# 08_-_LVDS.net
KiCad netlist of a schematic drawn in Altium Designer
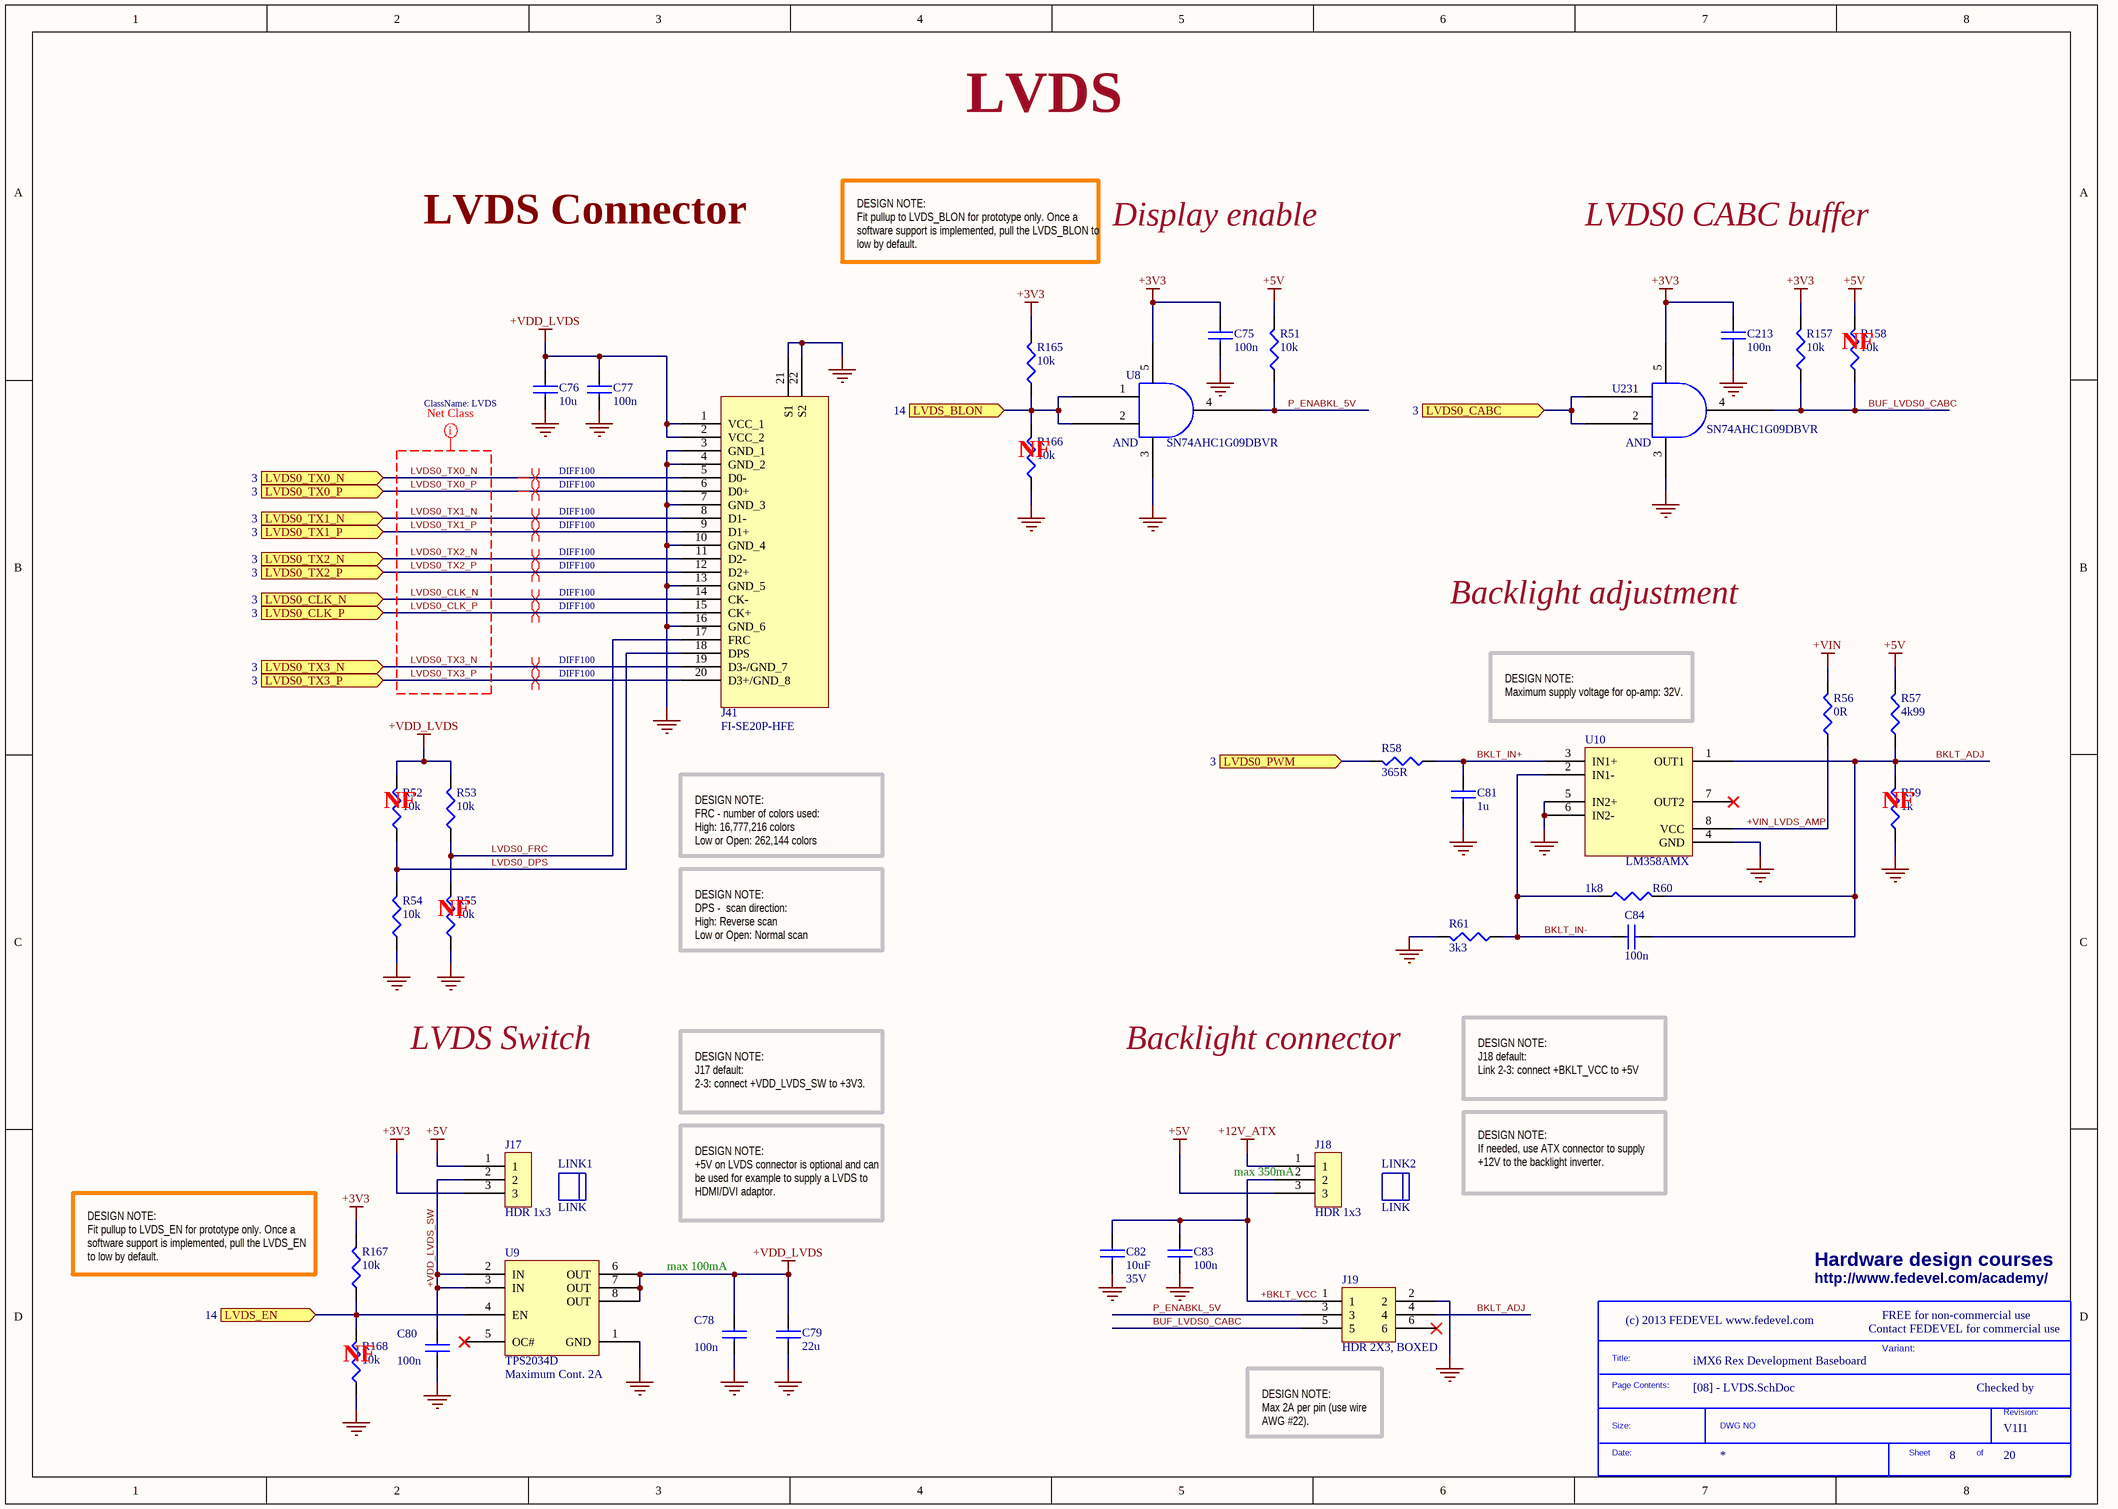
[diagram p0: [08] - LVDS.SchDoc]

(export (version "E")
  (design (tool "Eeschema 10.0.6"))
  (components
    (comp (ref "C75")
      (value "100n")
      (footprint "C0402")
      (description "CAP CER .10UF 50V X5R 10% 0402")
      (fields
        (field (name "MANUFACTURER") "TDK Corporation")
        (field (name "MANUFACTURER PART NUMBER") "C1005X5R1H104K")
      )
      (libsource (lib "Integrated_Library_RF_FEB_2012") (part "C1005X5R1H104K"))
    )
    (comp (ref "C76")
      (value "10u")
      (footprint "C0603")
      (description "CAP CER 10UF 6.3V X5R 20% 0603")
      (fields
        (field (name "MANUFACTURER") "TDK Corporation")
        (field (name "MANUFACTURER PART NUMBER") "C1608X5R0J106M")
      )
      (libsource (lib "Integrated_Library_RF_FEB_2012") (part "C1608X5R0J106M"))
    )
    (comp (ref "C77")
      (value "100n")
      (footprint "C0402")
      (description "CAP CER .10UF 50V X5R 10% 0402")
      (fields
        (field (name "MANUFACTURER") "TDK Corporation")
        (field (name "MANUFACTURER PART NUMBER") "C1005X5R1H104K")
      )
      (libsource (lib "Integrated_Library_RF_FEB_2012") (part "C1005X5R1H104K"))
    )
    (comp (ref "C78")
      (value "100n")
      (footprint "C0402")
      (description "CAP CER .10UF 50V X5R 10% 0402")
      (fields
        (field (name "MANUFACTURER") "TDK Corporation")
        (field (name "MANUFACTURER PART NUMBER") "C1005X5R1H104K")
      )
      (libsource (lib "Integrated_Library_RF_FEB_2012") (part "C1005X5R1H104K"))
    )
    (comp (ref "C79")
      (value "22u")
      (footprint "C0805")
      (description "CAP CER 22UF 16V 10% X5R 0805")
      (fields
        (field (name "MANUFACTURER") "TDK Corporation")
        (field (name "MANUFACTURER PART NUMBER") "C2012X5R1C226K")
        (field (name ".CHECKED PCB") "RF")
        (field (name ".CHECKED SCH") "RF")
      )
      (libsource (lib "Integrated_Library_RF_FEB_2012") (part "C2012X5R1C226K"))
    )
    (comp (ref "C80")
      (value "100n")
      (footprint "C0402")
      (description "CAP CER .10UF 50V X5R 10% 0402")
      (fields
        (field (name "MANUFACTURER") "TDK Corporation")
        (field (name "MANUFACTURER PART NUMBER") "C1005X5R1H104K")
      )
      (libsource (lib "Integrated_Library_RF_FEB_2012") (part "C1005X5R1H104K"))
    )
    (comp (ref "C81")
      (value "1u")
      (footprint "C0402")
      (description "CAP CER 1.0UF 16V X5R 0402")
      (fields
        (field (name "MANUFACTURER") "TDK Corporation")
        (field (name "MANUFACTURER PART NUMBER") "C1005X5R1C105K")
      )
      (libsource (lib "Integrated_Library_RF_FEB_2012") (part "C1005X5R1C105K"))
    )
    (comp (ref "C82")
      (value "10uF")
      (footprint "C1206")
      (description "CAP CER 10UF 35V X5R 1206")
      (fields
        (field (name "MANUFACTURER") "Murata Electronics North America")
        (field (name "MANUFACTURER PART NUMBER") "GRM31CR6YA106KA12L")
        (field (name "VOLTAGE - RATED") "35V")
      )
      (libsource (lib "Integrated_Library_RF_FEB_2012") (part "GRM31CR6YA106KA12L"))
    )
    (comp (ref "C83")
      (value "100n")
      (footprint "C0402")
      (description "CAP CER .10UF 50V X5R 10% 0402")
      (fields
        (field (name "MANUFACTURER") "TDK Corporation")
        (field (name "MANUFACTURER PART NUMBER") "C1005X5R1H104K")
      )
      (libsource (lib "Integrated_Library_RF_FEB_2012") (part "C1005X5R1H104K"))
    )
    (comp (ref "C84")
      (value "100n")
      (footprint "C0402")
      (description "CAP CER .10UF 50V X5R 10% 0402")
      (fields
        (field (name "MANUFACTURER") "TDK Corporation")
        (field (name "MANUFACTURER PART NUMBER") "C1005X5R1H104K")
      )
      (libsource (lib "Integrated_Library_RF_FEB_2012") (part "C1005X5R1H104K"))
    )
    (comp (ref "C213")
      (value "100n")
      (footprint "C0402")
      (description "CAP CER .10UF 50V X5R 10% 0402")
      (fields
        (field (name "MANUFACTURER") "TDK Corporation")
        (field (name "MANUFACTURER PART NUMBER") "C1005X5R1H104K")
      )
      (libsource (lib "Integrated_Library_RF_FEB_2012") (part "C1005X5R1H104K"))
    )
    (comp (ref "J17")
      (value "HDR 1x3")
      (footprint "Hdr_1x3_2.54mm")
      (description "BERGSTIK II .100\" SR STRAIGHT")
      (fields
        (field (name "MANUFACTURER") "FCI")
        (field (name "MANUFACTURER PART NUMBER") "68000-103HLF")
        (field (name ".CREATOR") "MM")
        (field (name ".CHECKED PCB") "MM")
        (field (name ".CHECKED SCH") "MM")
      )
      (libsource (lib "Integrated_Library_RF_FEB_2012") (part "68000-103HLF"))
    )
    (comp (ref "J18")
      (value "HDR 1x3")
      (footprint "Hdr_1x3_2.54mm")
      (description "BERGSTIK II .100\" SR STRAIGHT")
      (fields
        (field (name "MANUFACTURER") "FCI")
        (field (name "MANUFACTURER PART NUMBER") "68000-103HLF")
        (field (name ".CREATOR") "MM")
        (field (name ".CHECKED PCB") "MM")
        (field (name ".CHECKED SCH") "MM")
      )
      (libsource (lib "Integrated_Library_RF_FEB_2012") (part "68000-103HLF"))
    )
    (comp (ref "J19")
      (value "HDR 2X3, BOXED")
      (footprint "HDR_2x3_2.54mm_BOXED")
      (description "CONN HEADER 6POS DL STR GOLD")
      (fields
        (field (name "MANUFACTURER") "3M")
        (field (name "MANUFACTURER PART NUMBER") "30306-6002HB")
        (field (name ".CREATOR") "MM")
        (field (name ".CHECKED PCB") "MM")
        (field (name ".CHECKED SCH") "MM")
      )
      (libsource (lib "Integrated_Library_RF_FEB_2012") (part "30306-6002HB"))
    )
    (comp (ref "J41")
      (value "FI-SE20P-HFE")
      (footprint "FI-SE20P-HFE")
      (description "CONN RCPT 1.25MM 20POS SMD R/A")
      (fields
        (field (name "MANUFACTURER") "JAE Electronics")
        (field (name ".CREATOR") "MM")
        (field (name ".CHECKED PCB") "MM")
        (field (name ".CHECKED SCH") "MM")
      )
      (libsource (lib "Integrated_Library_RF_FEB_2012") (part "FI-SE20P-HFE"))
    )
    (comp (ref "LINK1")
      (value "LINK")
      (description "CONN JUMPER SHORTING .100\" GOLD")
      (fields
        (field (name "MANUFACTURER") "Sullins Connector Solutions")
        (field (name "MANUFACTURER PART NUMBER") "QPC02SXGN-RC")
        (field (name ".CHECKED SCH") "RF")
      )
      (libsource (lib "Integrated_Library_RF_FEB_2012") (part "QPC02SXGN-RC"))
    )
    (comp (ref "LINK2")
      (value "LINK")
      (description "CONN JUMPER SHORTING .100\" GOLD")
      (fields
        (field (name "MANUFACTURER") "Sullins Connector Solutions")
        (field (name "MANUFACTURER PART NUMBER") "QPC02SXGN-RC")
        (field (name ".CHECKED SCH") "RF")
      )
      (libsource (lib "Integrated_Library_RF_FEB_2012") (part "QPC02SXGN-RC"))
    )
    (comp (ref "R51")
      (value "10k")
      (footprint "R0402")
      (description "RES 10.0K OHM 1/16W 1% 0402 SMD")
      (fields
        (field (name "MANUFACTURER") "Yageo")
        (field (name "MANUFACTURER PART NUMBER") "RC0402FR-0710KL")
      )
      (libsource (lib "Integrated_Library_RF_FEB_2012") (part "RC0402FR-0710KL"))
    )
    (comp (ref "R52")
      (value "10k")
      (footprint "R0402")
      (description "RES 10.0K OHM 1/16W 1% 0402 SMD")
      (fields
        (field (name "MANUFACTURER") "Yageo")
        (field (name "MANUFACTURER PART NUMBER") "RC0402FR-0710KL")
      )
      (libsource (lib "Integrated_Library_RF_FEB_2012") (part "RC0402FR-0710KL"))
    )
    (comp (ref "R53")
      (value "10k")
      (footprint "R0402")
      (description "RES 10.0K OHM 1/16W 1% 0402 SMD")
      (fields
        (field (name "MANUFACTURER") "Yageo")
        (field (name "MANUFACTURER PART NUMBER") "RC0402FR-0710KL")
      )
      (libsource (lib "Integrated_Library_RF_FEB_2012") (part "RC0402FR-0710KL"))
    )
    (comp (ref "R54")
      (value "10k")
      (footprint "R0402")
      (description "RES 10.0K OHM 1/16W 1% 0402 SMD")
      (fields
        (field (name "MANUFACTURER") "Yageo")
        (field (name "MANUFACTURER PART NUMBER") "RC0402FR-0710KL")
      )
      (libsource (lib "Integrated_Library_RF_FEB_2012") (part "RC0402FR-0710KL"))
    )
    (comp (ref "R55")
      (value "10k")
      (footprint "R0402")
      (description "RES 10.0K OHM 1/16W 1% 0402 SMD")
      (fields
        (field (name "MANUFACTURER") "Yageo")
        (field (name "MANUFACTURER PART NUMBER") "RC0402FR-0710KL")
      )
      (libsource (lib "Integrated_Library_RF_FEB_2012") (part "RC0402FR-0710KL"))
    )
    (comp (ref "R56")
      (value "0R")
      (footprint "R0402")
      (description "RES 0.0 OHM 1/16W 0402 SMD")
      (fields
        (field (name "MANUFACTURER") "Yageo")
        (field (name "MANUFACTURER PART NUMBER") "RC0402JR-070RL")
      )
      (libsource (lib "Integrated_Library_RF_FEB_2012") (part "RC0402JR-070RL"))
    )
    (comp (ref "R57")
      (value "4k99")
      (footprint "R0402")
      (description "RES TF 4.99K OHM 1% 1/16W 0402")
      (fields
        (field (name "MANUFACTURER") "Stackpole Electronics Inc")
        (field (name "MANUFACTURER PART NUMBER") "RMCF0402FT4K99")
      )
      (libsource (lib "Integrated_Library_RF_FEB_2012") (part "RMCF0402FT4K99"))
    )
    (comp (ref "R58")
      (value "365R")
      (footprint "R0402")
      (description "RES TF 365 OHM 1% 1/16W 0402")
      (fields
        (field (name "MANUFACTURER") "Stackpole Electronics Inc")
        (field (name "MANUFACTURER PART NUMBER") "RMCF0402FT365R")
        (field (name ".CHECKED PCB") "RF")
        (field (name ".CHECKED SCH") "RF")
      )
      (libsource (lib "Integrated_Library_RF_FEB_2012") (part "RMCF0402FT365R"))
    )
    (comp (ref "R59")
      (value "1k")
      (footprint "R0402")
      (description "RES 1.00K OHM 1/16W 1% 0402 SMD")
      (fields
        (field (name "MANUFACTURER") "Yageo")
        (field (name "MANUFACTURER PART NUMBER") "RC0402FR-071KL")
      )
      (libsource (lib "Integrated_Library_RF_FEB_2012") (part "RC0402FR-071KL"))
    )
    (comp (ref "R60")
      (value "1k8")
      (footprint "R0402")
      (description "RES 1.80K OHM 1/16W 1% 0402 SMD")
      (fields
        (field (name "MANUFACTURER") "Vishay Dale")
        (field (name "MANUFACTURER PART NUMBER") "CRCW04021K80FKED")
        (field (name ".CHECKED PCB") "RF")
        (field (name ".CHECKED SCH") "RF")
      )
      (libsource (lib "Integrated_Library_RF_FEB_2012") (part "CRCW04021K80FKED"))
    )
    (comp (ref "R61")
      (value "3k3")
      (footprint "R0402")
      (description "RES 3.30K OHM 1/16W 1% 0402 SMD")
      (fields
        (field (name "MANUFACTURER") "Yageo")
        (field (name "MANUFACTURER PART NUMBER") "RC0402FR-073K3L")
      )
      (libsource (lib "Integrated_Library_RF_FEB_2012") (part "RC0402FR-073K3L"))
    )
    (comp (ref "R157")
      (value "10k")
      (footprint "R0402")
      (description "RES 10.0K OHM 1/16W 1% 0402 SMD")
      (fields
        (field (name "MANUFACTURER") "Yageo")
        (field (name "MANUFACTURER PART NUMBER") "RC0402FR-0710KL")
      )
      (libsource (lib "Integrated_Library_RF_FEB_2012") (part "RC0402FR-0710KL"))
    )
    (comp (ref "R158")
      (value "10k")
      (footprint "R0402")
      (description "RES 10.0K OHM 1/16W 1% 0402 SMD")
      (fields
        (field (name "MANUFACTURER") "Yageo")
        (field (name "MANUFACTURER PART NUMBER") "RC0402FR-0710KL")
      )
      (libsource (lib "Integrated_Library_RF_FEB_2012") (part "RC0402FR-0710KL"))
    )
    (comp (ref "R165")
      (value "10k")
      (footprint "R0402")
      (description "RES 10.0K OHM 1/16W 1% 0402 SMD")
      (fields
        (field (name "MANUFACTURER") "Yageo")
        (field (name "MANUFACTURER PART NUMBER") "RC0402FR-0710KL")
      )
      (libsource (lib "Integrated_Library_RF_FEB_2012") (part "RC0402FR-0710KL"))
    )
    (comp (ref "R166")
      (value "10k")
      (footprint "R0402")
      (description "RES 10.0K OHM 1/16W 1% 0402 SMD")
      (fields
        (field (name "MANUFACTURER") "Yageo")
        (field (name "MANUFACTURER PART NUMBER") "RC0402FR-0710KL")
      )
      (libsource (lib "Integrated_Library_RF_FEB_2012") (part "RC0402FR-0710KL"))
    )
    (comp (ref "R167")
      (value "10k")
      (footprint "R0402")
      (description "RES 10.0K OHM 1/16W 1% 0402 SMD")
      (fields
        (field (name "MANUFACTURER") "Yageo")
        (field (name "MANUFACTURER PART NUMBER") "RC0402FR-0710KL")
      )
      (libsource (lib "Integrated_Library_RF_FEB_2012") (part "RC0402FR-0710KL"))
    )
    (comp (ref "R168")
      (value "10k")
      (footprint "R0402")
      (description "RES 10.0K OHM 1/16W 1% 0402 SMD")
      (fields
        (field (name "MANUFACTURER") "Yageo")
        (field (name "MANUFACTURER PART NUMBER") "RC0402FR-0710KL")
      )
      (libsource (lib "Integrated_Library_RF_FEB_2012") (part "RC0402FR-0710KL"))
    )
    (comp (ref "U8")
      (value "SN74AHC1G09DBVR")
      (footprint "DBV_SOT_23_5")
      (description "IC GATE AND SGL 2INP SOT23-5")
      (fields
        (field (name "MANUFACTURER") "Texas Instruments")
        (field (name ".CREATOR") "MM")
        (field (name ".CHECKED PCB") "RF, used by MM")
        (field (name ".CHECKED SCH") "MM, checked by RF")
      )
      (libsource (lib "Integrated_Library_RF_FEB_2012") (part "SN74AHC1G09DBVR"))
    )
    (comp (ref "U9")
      (value "TPS2034D")
      (footprint "8_SOIC_3.9MM")
      (description "IC 3.0A POWER DIST SWITCH 8-SOIC")
      (fields
        (field (name "MANUFACTURER") "Texas Instruments")
        (field (name ".CHECKED PCB") "RF")
        (field (name ".CHECKED SCH") "RF")
      )
      (libsource (lib "Integrated_Library_RF_FEB_2012") (part "TPS2034D"))
    )
    (comp (ref "U10")
      (value "LM358AMX")
      (footprint "8_SOIC_3.9MM")
      (description "IC OPAMP DUAL 0-70DEG C 8-SOIC")
      (fields
        (field (name "MANUFACTURER") "Fairchild Semiconductor")
        (field (name ".CHECKED PCB") "RF")
        (field (name ".CHECKED SCH") "RF")
      )
      (libsource (lib "Integrated_Library_RF_FEB_2012") (part "LM358AMX"))
    )
    (comp (ref "U23")
      (value "SN74AHC1G09DBVR")
      (footprint "DBV_SOT_23_5")
      (description "IC GATE AND SGL 2INP SOT23-5")
      (fields
        (field (name "MANUFACTURER") "Texas Instruments")
        (field (name ".CREATOR") "MM")
        (field (name ".CHECKED PCB") "RF, used by MM")
        (field (name ".CHECKED SCH") "MM, checked by RF")
      )
      (libsource (lib "Integrated_Library_RF_FEB_2012") (part "SN74AHC1G09DBVR"))
    )
  )
  (nets
    (net (code "1") (name "+3V3") (class "Default")
      (node (ref "C213") (pin "1") (pinfunction "1_1") (pintype "passive"))
      (node (ref "C75") (pin "1") (pinfunction "1_1") (pintype "passive"))
      (node (ref "J17") (pin "3") (pinfunction "3_3") (pintype "passive"))
      (node (ref "R157") (pin "2") (pinfunction "2_2") (pintype "passive"))
      (node (ref "R165") (pin "2") (pinfunction "2_2") (pintype "passive"))
      (node (ref "R167") (pin "2") (pinfunction "2_2") (pintype "passive"))
      (node (ref "U23") (pin "5") (pinfunction "VCC_5") (pintype "power_in"))
      (node (ref "U8") (pin "5") (pinfunction "VCC_5") (pintype "power_in"))
    )
    (net (code "2") (name "+5V") (class "Default")
      (node (ref "J17") (pin "1") (pinfunction "1_1") (pintype "passive"))
      (node (ref "J18") (pin "3") (pinfunction "3_3") (pintype "passive"))
      (node (ref "R158") (pin "2") (pinfunction "2_2") (pintype "passive"))
      (node (ref "R51") (pin "2") (pinfunction "2_2") (pintype "passive"))
      (node (ref "R57") (pin "2") (pinfunction "2_2") (pintype "passive"))
    )
    (net (code "3") (name "+12V_ATX") (class "Default")
      (node (ref "J18") (pin "1") (pinfunction "1_1") (pintype "passive"))
    )
    (net (code "4") (name "+VDD_LVDS") (class "Default")
      (node (ref "C76") (pin "1") (pinfunction "1_1") (pintype "passive"))
      (node (ref "C77") (pin "1") (pinfunction "1_1") (pintype "passive"))
      (node (ref "C78") (pin "1") (pinfunction "1_1") (pintype "passive"))
      (node (ref "C79") (pin "1") (pinfunction "1_1") (pintype "passive"))
      (node (ref "J41") (pin "1") (pinfunction "VCC_1_1") (pintype "passive"))
      (node (ref "J41") (pin "2") (pinfunction "VCC_2_2") (pintype "passive"))
      (node (ref "R52") (pin "2") (pinfunction "2_2") (pintype "passive"))
      (node (ref "R53") (pin "2") (pinfunction "2_2") (pintype "passive"))
      (node (ref "U9") (pin "6") (pinfunction "OUT_6") (pintype "passive"))
      (node (ref "U9") (pin "7") (pinfunction "OUT_7") (pintype "passive"))
      (node (ref "U9") (pin "8") (pinfunction "OUT_8") (pintype "passive"))
    )
    (net (code "5") (name "+VIN") (class "Default")
      (node (ref "R56") (pin "2") (pinfunction "2_2") (pintype "passive"))
    )
    (net (code "6") (name "/+BKLT_VCC") (class "Default")
      (node (ref "C82") (pin "1") (pinfunction "1_1") (pintype "passive"))
      (node (ref "C83") (pin "1") (pinfunction "1_1") (pintype "passive"))
      (node (ref "J18") (pin "2") (pinfunction "2_2") (pintype "passive"))
      (node (ref "J19") (pin "1") (pinfunction "1_1") (pintype "passive"))
    )
    (net (code "7") (name "/+VDD_LVDS_SW") (class "Default")
      (node (ref "C80") (pin "1") (pinfunction "1_1") (pintype "passive"))
      (node (ref "J17") (pin "2") (pinfunction "2_2") (pintype "passive"))
      (node (ref "U9") (pin "2") (pinfunction "IN_2") (pintype "passive"))
      (node (ref "U9") (pin "3") (pinfunction "IN_3") (pintype "passive"))
    )
    (net (code "8") (name "/+VIN_LVDS_AMP") (class "Default")
      (node (ref "R56") (pin "1") (pinfunction "1_1") (pintype "passive"))
      (node (ref "U10") (pin "8") (pinfunction "VCC_8") (pintype "passive"))
    )
    (net (code "9") (name "/BKLT_ADJ") (class "Default")
      (node (ref "C84") (pin "2") (pinfunction "2_2") (pintype "passive"))
      (node (ref "J19") (pin "4") (pinfunction "4_4") (pintype "passive"))
      (node (ref "R57") (pin "1") (pinfunction "1_1") (pintype "passive"))
      (node (ref "R59") (pin "2") (pinfunction "2_2") (pintype "passive"))
      (node (ref "R60") (pin "2") (pinfunction "2_2") (pintype "passive"))
      (node (ref "U10") (pin "1") (pinfunction "OUT1_1") (pintype "passive"))
    )
    (net (code "10") (name "/BKLT_IN+") (class "Default")
      (node (ref "C81") (pin "1") (pinfunction "1_1") (pintype "passive"))
      (node (ref "R58") (pin "1") (pinfunction "1_1") (pintype "passive"))
      (node (ref "U10") (pin "3") (pinfunction "IN1+_3") (pintype "passive"))
    )
    (net (code "11") (name "/BKLT_IN-") (class "Default")
      (node (ref "C84") (pin "1") (pinfunction "1_1") (pintype "passive"))
      (node (ref "R60") (pin "1") (pinfunction "1_1") (pintype "passive"))
      (node (ref "R61") (pin "1") (pinfunction "1_1") (pintype "passive"))
      (node (ref "U10") (pin "2") (pinfunction "IN1-_2") (pintype "passive"))
    )
    (net (code "12") (name "/BUF_LVDS0_CABC") (class "Default")
      (node (ref "J19") (pin "5") (pinfunction "5_5") (pintype "passive"))
      (node (ref "R157") (pin "1") (pinfunction "1_1") (pintype "passive"))
      (node (ref "R158") (pin "1") (pinfunction "1_1") (pintype "passive"))
      (node (ref "U23") (pin "4") (pinfunction "Y_4") (pintype "passive"))
    )
    (net (code "13") (name "/LVDS0_CABC") (class "Default")
      (node (ref "U23") (pin "1") (pinfunction "A_1") (pintype "passive"))
      (node (ref "U23") (pin "2") (pinfunction "B_2") (pintype "passive"))
    )
    (net (code "14") (name "/LVDS0_CLK_N") (class "Default")
      (node (ref "J41") (pin "14") (pinfunction "CK-_14") (pintype "passive"))
    )
    (net (code "15") (name "/LVDS0_CLK_P") (class "Default")
      (node (ref "J41") (pin "15") (pinfunction "CK+_15") (pintype "passive"))
    )
    (net (code "16") (name "/LVDS0_DPS") (class "Default")
      (node (ref "J41") (pin "18") (pinfunction "DPS_18") (pintype "passive"))
      (node (ref "R52") (pin "1") (pinfunction "1_1") (pintype "passive"))
      (node (ref "R54") (pin "2") (pinfunction "2_2") (pintype "passive"))
    )
    (net (code "17") (name "/LVDS0_FRC") (class "Default")
      (node (ref "J41") (pin "17") (pinfunction "FRC_17") (pintype "passive"))
      (node (ref "R53") (pin "1") (pinfunction "1_1") (pintype "passive"))
      (node (ref "R55") (pin "2") (pinfunction "2_2") (pintype "passive"))
    )
    (net (code "18") (name "/LVDS0_PWM") (class "Default")
      (node (ref "R58") (pin "2") (pinfunction "2_2") (pintype "passive"))
    )
    (net (code "19") (name "/LVDS0_TX0_N") (class "Default")
      (node (ref "J41") (pin "5") (pinfunction "D0-_5") (pintype "passive"))
    )
    (net (code "20") (name "/LVDS0_TX0_P") (class "Default")
      (node (ref "J41") (pin "6") (pinfunction "D0+_6") (pintype "passive"))
    )
    (net (code "21") (name "/LVDS0_TX1_N") (class "Default")
      (node (ref "J41") (pin "8") (pinfunction "D1-_8") (pintype "passive"))
    )
    (net (code "22") (name "/LVDS0_TX1_P") (class "Default")
      (node (ref "J41") (pin "9") (pinfunction "D1+_9") (pintype "passive"))
    )
    (net (code "23") (name "/LVDS0_TX2_N") (class "Default")
      (node (ref "J41") (pin "11") (pinfunction "D2-_11") (pintype "passive"))
    )
    (net (code "24") (name "/LVDS0_TX2_P") (class "Default")
      (node (ref "J41") (pin "12") (pinfunction "D2+_12") (pintype "passive"))
    )
    (net (code "25") (name "/LVDS0_TX3_N") (class "Default")
      (node (ref "J41") (pin "19") (pinfunction "D3-/GND_7_19") (pintype "passive"))
    )
    (net (code "26") (name "/LVDS0_TX3_P") (class "Default")
      (node (ref "J41") (pin "20") (pinfunction "D3+/GND_8_20") (pintype "passive"))
    )
    (net (code "27") (name "/LVDS_BLON") (class "Default")
      (node (ref "R165") (pin "1") (pinfunction "1_1") (pintype "passive"))
      (node (ref "R166") (pin "2") (pinfunction "2_2") (pintype "passive"))
      (node (ref "U8") (pin "1") (pinfunction "A_1") (pintype "passive"))
      (node (ref "U8") (pin "2") (pinfunction "B_2") (pintype "passive"))
    )
    (net (code "28") (name "/LVDS_EN") (class "Default")
      (node (ref "R167") (pin "1") (pinfunction "1_1") (pintype "passive"))
      (node (ref "R168") (pin "2") (pinfunction "2_2") (pintype "passive"))
      (node (ref "U9") (pin "4") (pinfunction "EN_4") (pintype "passive"))
    )
    (net (code "29") (name "/P_ENABKL_5V") (class "Default")
      (node (ref "J19") (pin "3") (pinfunction "3_3") (pintype "passive"))
      (node (ref "R51") (pin "1") (pinfunction "1_1") (pintype "passive"))
      (node (ref "U8") (pin "4") (pinfunction "Y_4") (pintype "passive"))
    )
    (net (code "30") (name "GND") (class "Default")
      (node (ref "C213") (pin "2") (pinfunction "2_2") (pintype "passive"))
      (node (ref "C75") (pin "2") (pinfunction "2_2") (pintype "passive"))
      (node (ref "C76") (pin "2") (pinfunction "2_2") (pintype "passive"))
      (node (ref "C77") (pin "2") (pinfunction "2_2") (pintype "passive"))
      (node (ref "C78") (pin "2") (pinfunction "2_2") (pintype "passive"))
      (node (ref "C79") (pin "2") (pinfunction "2_2") (pintype "passive"))
      (node (ref "C80") (pin "2") (pinfunction "2_2") (pintype "passive"))
      (node (ref "C81") (pin "2") (pinfunction "2_2") (pintype "passive"))
      (node (ref "C82") (pin "2") (pinfunction "2_2") (pintype "passive"))
      (node (ref "C83") (pin "2") (pinfunction "2_2") (pintype "passive"))
      (node (ref "J19") (pin "2") (pinfunction "2_2") (pintype "passive"))
      (node (ref "J41") (pin "10") (pinfunction "GND_4_10") (pintype "passive"))
      (node (ref "J41") (pin "13") (pinfunction "GND_5_13") (pintype "passive"))
      (node (ref "J41") (pin "16") (pinfunction "GND_6_16") (pintype "passive"))
      (node (ref "J41") (pin "21") (pinfunction "S1_21") (pintype "passive"))
      (node (ref "J41") (pin "22") (pinfunction "S2_22") (pintype "passive"))
      (node (ref "J41") (pin "3") (pinfunction "GND_1_3") (pintype "passive"))
      (node (ref "J41") (pin "4") (pinfunction "GND_2_4") (pintype "passive"))
      (node (ref "J41") (pin "7") (pinfunction "GND_3_7") (pintype "passive"))
      (node (ref "R166") (pin "1") (pinfunction "1_1") (pintype "passive"))
      (node (ref "R168") (pin "1") (pinfunction "1_1") (pintype "passive"))
      (node (ref "R54") (pin "1") (pinfunction "1_1") (pintype "passive"))
      (node (ref "R55") (pin "1") (pinfunction "1_1") (pintype "passive"))
      (node (ref "R59") (pin "1") (pinfunction "1_1") (pintype "passive"))
      (node (ref "R61") (pin "2") (pinfunction "2_2") (pintype "passive"))
      (node (ref "U10") (pin "4") (pinfunction "GND_4") (pintype "passive"))
      (node (ref "U10") (pin "5") (pinfunction "IN2+_5") (pintype "passive"))
      (node (ref "U10") (pin "6") (pinfunction "IN2-_6") (pintype "passive"))
      (node (ref "U23") (pin "3") (pinfunction "GND_3") (pintype "power_in"))
      (node (ref "U8") (pin "3") (pinfunction "GND_3") (pintype "power_in"))
      (node (ref "U9") (pin "1") (pinfunction "GND_1") (pintype "passive"))
    )
    (net (code "31") (name "unconnected-(J19-Pad6)") (class "Default")
      (node (ref "J19") (pin "6") (pinfunction "6_6") (pintype "passive+no_connect"))
    )
    (net (code "32") (name "unconnected-(U9-OC#-Pad5)") (class "Default")
      (node (ref "U9") (pin "5") (pinfunction "OC#_5") (pintype "passive+no_connect"))
    )
    (net (code "33") (name "unconnected-(U10-OUT2-Pad7)") (class "Default")
      (node (ref "U10") (pin "7") (pinfunction "OUT2_7") (pintype "passive+no_connect"))
    )
  )
)
